# top.net
KiCad netlist of a schematic drawn in Altium Designer
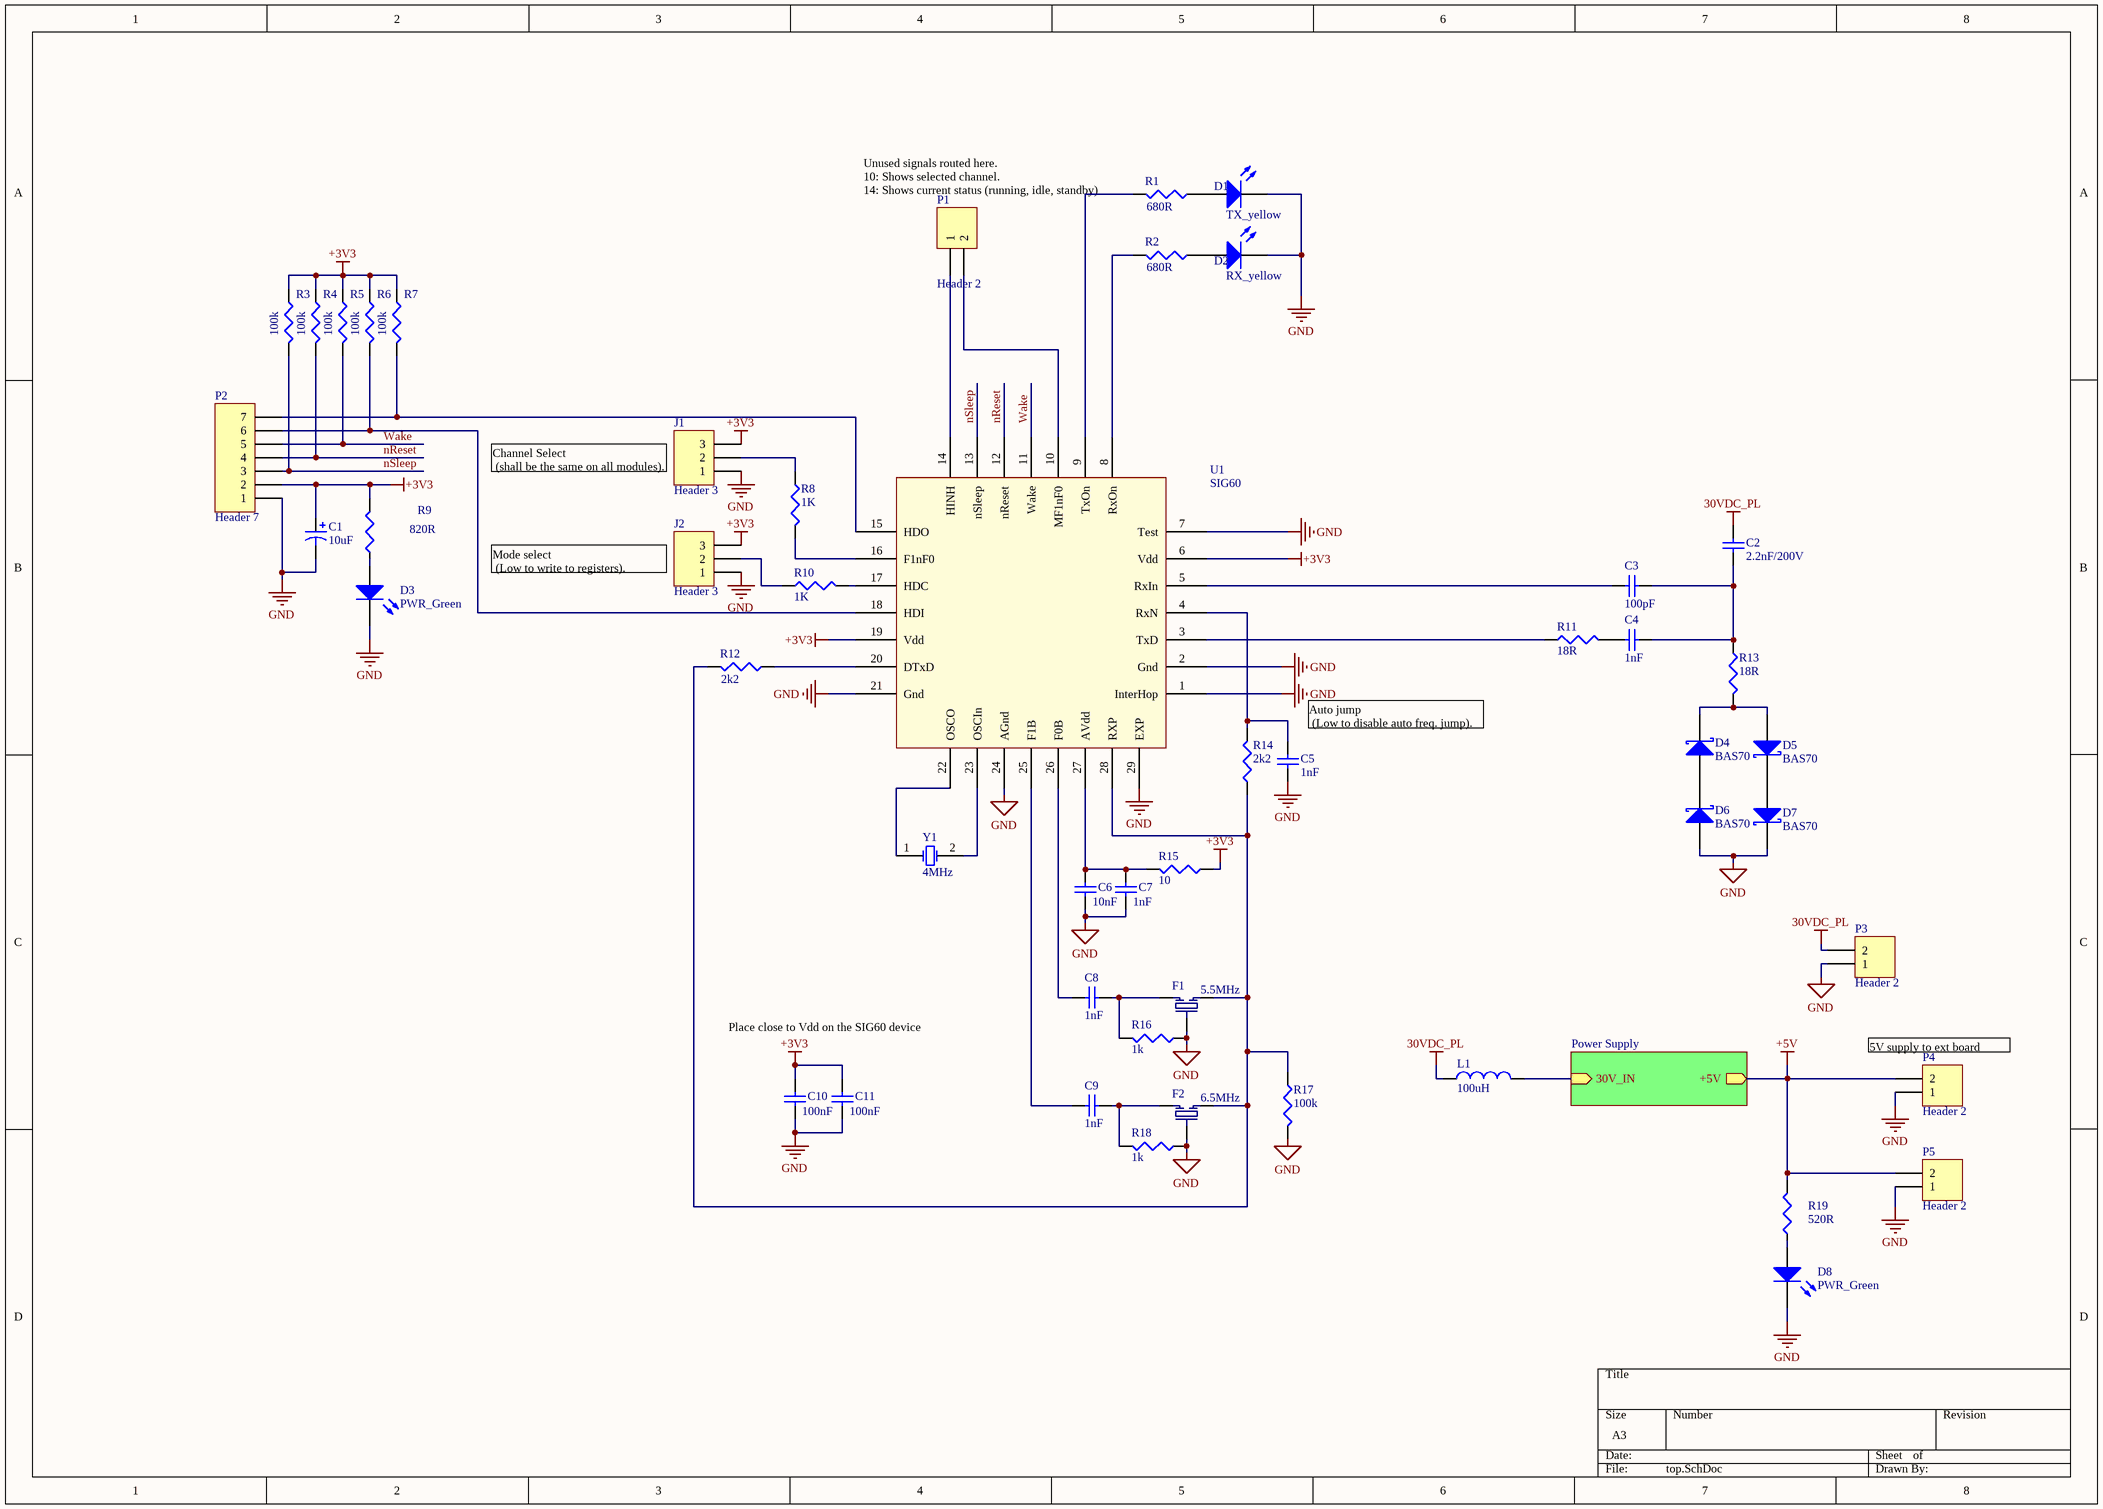
[diagram p0: top.SchDoc]

(export (version "E")
  (design (tool "Eeschema 10.0.6"))
  (components
    (comp (ref "C1")
      (value "10uF")
      (footprint "C0805")
      (description "Polarized Capacitor (Surface Mount)")
      (fields (field (name "Comment") "Cap Pol3") (field (name "PUBLISHER") "Altium Limited"))
      (libsource (lib "Miscellaneous Devices") (part "Cap Pol3"))
    )
    (comp (ref "C2")
      (value "2.2nF/200V")
      (footprint "6-0805_N")
      (description "Capacitor (Semiconductor SIM Model)")
      (fields (field (name "Comment") "Cap Semi") (field (name "PUBLISHER") "Altium Limited"))
      (libsource (lib "Miscellaneous Devices") (part "Cap Semi"))
    )
    (comp (ref "C3")
      (value "100pF")
      (footprint "6-0805_N")
      (description "Capacitor (Semiconductor SIM Model)")
      (fields (field (name "Comment") "Cap Semi") (field (name "PUBLISHER") "Altium Limited"))
      (libsource (lib "Miscellaneous Devices") (part "Cap Semi"))
    )
    (comp (ref "C4")
      (value "1nF")
      (footprint "6-0805_N")
      (description "Capacitor (Semiconductor SIM Model)")
      (fields (field (name "Comment") "Cap Semi") (field (name "PUBLISHER") "Altium Limited"))
      (libsource (lib "Miscellaneous Devices") (part "Cap Semi"))
    )
    (comp (ref "C5")
      (value "1nF")
      (footprint "6-0805_N")
      (description "Capacitor (Semiconductor SIM Model)")
      (fields (field (name "Comment") "Cap Semi") (field (name "PUBLISHER") "Altium Limited"))
      (libsource (lib "Miscellaneous Devices") (part "Cap Semi"))
    )
    (comp (ref "C6")
      (value "10nF")
      (footprint "6-0805_N")
      (description "Capacitor (Semiconductor SIM Model)")
      (fields (field (name "Comment") "Cap Semi") (field (name "PUBLISHER") "Altium Limited"))
      (libsource (lib "Miscellaneous Devices") (part "Cap Semi"))
    )
    (comp (ref "C7")
      (value "1nF")
      (footprint "6-0805_N")
      (description "Capacitor (Semiconductor SIM Model)")
      (fields (field (name "Comment") "Cap Semi") (field (name "PUBLISHER") "Altium Limited"))
      (libsource (lib "Miscellaneous Devices") (part "Cap Semi"))
    )
    (comp (ref "C8")
      (value "1nF")
      (footprint "6-0805_N")
      (description "Capacitor (Semiconductor SIM Model)")
      (fields (field (name "Comment") "Cap Semi") (field (name "PUBLISHER") "Altium Limited"))
      (libsource (lib "Miscellaneous Devices") (part "Cap Semi"))
    )
    (comp (ref "C9")
      (value "1nF")
      (footprint "6-0805_N")
      (description "Capacitor (Semiconductor SIM Model)")
      (fields (field (name "Comment") "Cap Semi") (field (name "PUBLISHER") "Altium Limited"))
      (libsource (lib "Miscellaneous Devices") (part "Cap Semi"))
    )
    (comp (ref "C10")
      (value "100nF")
      (footprint "6-0805_N")
      (description "Capacitor (Semiconductor SIM Model)")
      (fields (field (name "Comment") "Cap Semi") (field (name "PUBLISHER") "Altium Limited"))
      (libsource (lib "Miscellaneous Devices") (part "Cap Semi"))
    )
    (comp (ref "C11")
      (value "100nF")
      (footprint "6-0805_N")
      (description "Capacitor (Semiconductor SIM Model)")
      (fields (field (name "Comment") "Cap Semi") (field (name "PUBLISHER") "Altium Limited"))
      (libsource (lib "Miscellaneous Devices") (part "Cap Semi"))
    )
    (comp (ref "D1")
      (value "TX_yellow")
      (footprint "6-0805_L")
      (description "Typical RED, GREEN, YELLOW, AMBER GaAs LED")
      (fields (field (name "PUBLISHER") "Altium Limited"))
      (libsource (lib "Miscellaneous Devices") (part "LED2"))
    )
    (comp (ref "D2")
      (value "RX_yellow")
      (footprint "6-0805_L")
      (description "Typical RED, GREEN, YELLOW, AMBER GaAs LED")
      (fields (field (name "PUBLISHER") "Altium Limited"))
      (libsource (lib "Miscellaneous Devices") (part "LED2"))
    )
    (comp (ref "D3")
      (value "PWR_Green")
      (footprint "6-0805_L")
      (description "Typical RED, GREEN, YELLOW, AMBER GaAs LED")
      (fields (field (name "PUBLISHER") "Altium Limited"))
      (libsource (lib "Miscellaneous Devices") (part "LED2"))
    )
    (comp (ref "D4")
      (value "BAS70")
      (footprint "SOT-23_N")
      (description "Silicon AF Schottky Diode for High-Speed Switching")
      (fields (field (name "PUBLISHER") "Altium Limited"))
      (libsource (lib "Miscellaneous Devices") (part "Diode BAS70"))
    )
    (comp (ref "D5")
      (value "BAS70")
      (footprint "SOT-23_N")
      (description "Silicon AF Schottky Diode for High-Speed Switching")
      (fields (field (name "PUBLISHER") "Altium Limited"))
      (libsource (lib "Miscellaneous Devices") (part "Diode BAS70"))
    )
    (comp (ref "D6")
      (value "BAS70")
      (footprint "SOT-23_N")
      (description "Silicon AF Schottky Diode for High-Speed Switching")
      (fields (field (name "PUBLISHER") "Altium Limited"))
      (libsource (lib "Miscellaneous Devices") (part "Diode BAS70"))
    )
    (comp (ref "D7")
      (value "BAS70")
      (footprint "SOT-23_N")
      (description "Silicon AF Schottky Diode for High-Speed Switching")
      (fields (field (name "PUBLISHER") "Altium Limited"))
      (libsource (lib "Miscellaneous Devices") (part "Diode BAS70"))
    )
    (comp (ref "D8")
      (value "PWR_Green")
      (footprint "6-0805_L")
      (description "Typical RED, GREEN, YELLOW, AMBER GaAs LED")
      (fields (field (name "PUBLISHER") "Altium Limited"))
      (libsource (lib "Miscellaneous Devices") (part "LED2"))
    )
    (comp (ref "F1")
      (value "5.5MHz")
      (footprint "HDR1X3")
      (description "Header, 3-Pin")
      (fields (field (name "PUBLISHER") "Altium Limited"))
      (libsource (lib "new_library") (part "Ceramic Filters"))
    )
    (comp (ref "F2")
      (value "6.5MHz")
      (footprint "HDR1X3")
      (description "Header, 3-Pin")
      (fields (field (name "PUBLISHER") "Altium Limited"))
      (libsource (lib "new_library") (part "Ceramic Filters"))
    )
    (comp (ref "J1")
      (value "Header 3")
      (footprint "HDR1X3")
      (description "Header, 3-Pin")
      (fields (field (name "PUBLISHER") "Altium Limited"))
      (libsource (lib "Miscellaneous Connectors") (part "Header 3"))
    )
    (comp (ref "J2")
      (value "Header 3")
      (footprint "HDR1X3")
      (description "Header, 3-Pin")
      (fields (field (name "PUBLISHER") "Altium Limited"))
      (libsource (lib "Miscellaneous Connectors") (part "Header 3"))
    )
    (comp (ref "L1")
      (value "100uH")
      (footprint "WE_74477006")
      (description "Header, 3-Pin")
      (fields (field (name "PUBLISHER") "Altium Limited"))
      (libsource (lib "new_library") (part "Inductor"))
    )
    (comp (ref "P1")
      (value "Header 2")
      (footprint "HDR1X2")
      (description "Header, 2-Pin")
      (fields (field (name "PUBLISHER") "Altium Limited"))
      (libsource (lib "Miscellaneous Connectors") (part "Header 2"))
    )
    (comp (ref "P2")
      (value "Header 7")
      (footprint "HDR1X7")
      (description "Header, 7-Pin")
      (fields (field (name "PUBLISHER") "Altium Limited"))
      (libsource (lib "Miscellaneous Connectors") (part "Header 7"))
    )
    (comp (ref "P3")
      (value "Header 2")
      (footprint "HDR1X2")
      (description "Header, 2-Pin")
      (fields (field (name "PUBLISHER") "Altium Limited"))
      (libsource (lib "Miscellaneous Connectors") (part "Header 2"))
    )
    (comp (ref "P4")
      (value "Header 2")
      (footprint "HDR1X2")
      (description "Header, 2-Pin")
      (fields (field (name "PUBLISHER") "Altium Limited"))
      (libsource (lib "Miscellaneous Connectors") (part "Header 2"))
    )
    (comp (ref "P5")
      (value "Header 2")
      (footprint "HDR1X2")
      (description "Header, 2-Pin")
      (fields (field (name "PUBLISHER") "Altium Limited"))
      (libsource (lib "Miscellaneous Connectors") (part "Header 2"))
    )
    (comp (ref "R1")
      (value "680R")
      (footprint "6-0805_L")
      (description "Resistor")
      (fields (field (name "Comment") "Res3") (field (name "PUBLISHER") "Altium Limited"))
      (libsource (lib "Miscellaneous Devices") (part "Res3"))
    )
    (comp (ref "R2")
      (value "680R")
      (footprint "6-0805_L")
      (description "Resistor")
      (fields (field (name "Comment") "Res3") (field (name "PUBLISHER") "Altium Limited"))
      (libsource (lib "Miscellaneous Devices") (part "Res3"))
    )
    (comp (ref "R3")
      (value "100k")
      (footprint "6-0805_L")
      (description "Resistor")
      (fields (field (name "Comment") "Res3") (field (name "PUBLISHER") "Altium Limited"))
      (libsource (lib "Miscellaneous Devices") (part "Res3"))
    )
    (comp (ref "R4")
      (value "100k")
      (footprint "6-0805_L")
      (description "Resistor")
      (fields (field (name "Comment") "Res3") (field (name "PUBLISHER") "Altium Limited"))
      (libsource (lib "Miscellaneous Devices") (part "Res3"))
    )
    (comp (ref "R5")
      (value "100k")
      (footprint "6-0805_L")
      (description "Resistor")
      (fields (field (name "Comment") "Res3") (field (name "PUBLISHER") "Altium Limited"))
      (libsource (lib "Miscellaneous Devices") (part "Res3"))
    )
    (comp (ref "R6")
      (value "100k")
      (footprint "6-0805_L")
      (description "Resistor")
      (fields (field (name "Comment") "Res3") (field (name "PUBLISHER") "Altium Limited"))
      (libsource (lib "Miscellaneous Devices") (part "Res3"))
    )
    (comp (ref "R7")
      (value "100k")
      (footprint "6-0805_L")
      (description "Resistor")
      (fields (field (name "Comment") "Res3") (field (name "PUBLISHER") "Altium Limited"))
      (libsource (lib "Miscellaneous Devices") (part "Res3"))
    )
    (comp (ref "R8")
      (value "1K")
      (footprint "6-0805_L")
      (description "Resistor")
      (fields (field (name "Comment") "Res3") (field (name "PUBLISHER") "Altium Limited"))
      (libsource (lib "Miscellaneous Devices") (part "Res3"))
    )
    (comp (ref "R9")
      (value "820R")
      (footprint "6-0805_L")
      (description "Resistor")
      (fields (field (name "Comment") "Res3") (field (name "PUBLISHER") "Altium Limited"))
      (libsource (lib "Miscellaneous Devices") (part "Res3"))
    )
    (comp (ref "R10")
      (value "1K")
      (footprint "6-0805_L")
      (description "Resistor")
      (fields (field (name "Comment") "Res3") (field (name "PUBLISHER") "Altium Limited"))
      (libsource (lib "Miscellaneous Devices") (part "Res3"))
    )
    (comp (ref "R11")
      (value "18R")
      (footprint "6-0805_L")
      (description "Resistor")
      (fields (field (name "Comment") "Res3") (field (name "PUBLISHER") "Altium Limited"))
      (libsource (lib "Miscellaneous Devices") (part "Res3"))
    )
    (comp (ref "R12")
      (value "2k2")
      (footprint "6-0805_L")
      (description "Resistor")
      (fields (field (name "Comment") "Res3") (field (name "PUBLISHER") "Altium Limited"))
      (libsource (lib "Miscellaneous Devices") (part "Res3"))
    )
    (comp (ref "R13")
      (value "18R")
      (footprint "6-0805_L")
      (description "Resistor")
      (fields (field (name "Comment") "Res3") (field (name "PUBLISHER") "Altium Limited"))
      (libsource (lib "Miscellaneous Devices") (part "Res3"))
    )
    (comp (ref "R14")
      (value "2k2")
      (footprint "6-0805_L")
      (description "Resistor")
      (fields (field (name "Comment") "Res3") (field (name "PUBLISHER") "Altium Limited"))
      (libsource (lib "Miscellaneous Devices") (part "Res3"))
    )
    (comp (ref "R15")
      (value "10")
      (footprint "6-0805_L")
      (description "Resistor")
      (fields (field (name "Comment") "Res3") (field (name "PUBLISHER") "Altium Limited"))
      (libsource (lib "Miscellaneous Devices") (part "Res3"))
    )
    (comp (ref "R16")
      (value "1k")
      (footprint "6-0805_L")
      (description "Resistor")
      (fields (field (name "Comment") "Res3") (field (name "PUBLISHER") "Altium Limited"))
      (libsource (lib "Miscellaneous Devices") (part "Res3"))
    )
    (comp (ref "R17")
      (value "100k")
      (footprint "6-0805_L")
      (description "Resistor")
      (fields (field (name "Comment") "Res3") (field (name "PUBLISHER") "Altium Limited"))
      (libsource (lib "Miscellaneous Devices") (part "Res3"))
    )
    (comp (ref "R18")
      (value "1k")
      (footprint "6-0805_L")
      (description "Resistor")
      (fields (field (name "Comment") "Res3") (field (name "PUBLISHER") "Altium Limited"))
      (libsource (lib "Miscellaneous Devices") (part "Res3"))
    )
    (comp (ref "R19")
      (value "520R")
      (footprint "6-0805_L")
      (description "Resistor")
      (fields (field (name "Comment") "Res3") (field (name "PUBLISHER") "Altium Limited"))
      (libsource (lib "Miscellaneous Devices") (part "Res3"))
    )
    (comp (ref "U1")
      (value "SIG60")
      (footprint "QFN65P600X600X90-28N")
      (description "SIG60 device. UART to PLC device.")
      (libsource (lib "new_library") (part "SIG60"))
    )
    (comp (ref "Y1")
      (value "4MHz")
      (footprint "R38")
      (description "Crystal Oscillator")
      (fields (field (name "PUBLISHER") "Altium Limited"))
      (libsource (lib "Miscellaneous Devices") (part "XTAL"))
    )
  )
  (nets
    (net (code "1") (name "+3V3") (class "Default")
      (node (ref "C1") (pin "1") (pinfunction "1_1") (pintype "passive"))
      (node (ref "C10") (pin "2") (pinfunction "2_2") (pintype "passive"))
      (node (ref "C11") (pin "2") (pinfunction "2_2") (pintype "passive"))
      (node (ref "J1") (pin "3") (pinfunction "3_3") (pintype "passive"))
      (node (ref "J2") (pin "3") (pinfunction "3_3") (pintype "passive"))
      (node (ref "P2") (pin "2") (pinfunction "2_2") (pintype "passive"))
      (node (ref "R15") (pin "1") (pinfunction "1_1") (pintype "passive"))
      (node (ref "R3") (pin "1") (pinfunction "1_1") (pintype "passive"))
      (node (ref "R4") (pin "1") (pinfunction "1_1") (pintype "passive"))
      (node (ref "R5") (pin "1") (pinfunction "1_1") (pintype "passive"))
      (node (ref "R6") (pin "1") (pinfunction "1_1") (pintype "passive"))
      (node (ref "R7") (pin "1") (pinfunction "1_1") (pintype "passive"))
      (node (ref "R9") (pin "2") (pinfunction "2_2") (pintype "passive"))
      (node (ref "U1") (pin "19") (pinfunction "Vdd_19") (pintype "power_in"))
      (node (ref "U1") (pin "6") (pinfunction "Vdd_6") (pintype "power_in"))
    )
    (net (code "2") (name "+5V") (class "Default")
      (node (ref "P4") (pin "2") (pinfunction "2_2") (pintype "passive"))
      (node (ref "P5") (pin "2") (pinfunction "2_2") (pintype "passive"))
      (node (ref "R19") (pin "2") (pinfunction "2_2") (pintype "passive"))
    )
    (net (code "3") (name "/30V_IN") (class "Default")
      (node (ref "L1") (pin "2") (pinfunction "2_2") (pintype "passive"))
    )
    (net (code "4") (name "/Wake") (class "Default")
      (node (ref "P2") (pin "5") (pinfunction "5_5") (pintype "passive"))
      (node (ref "R5") (pin "2") (pinfunction "2_2") (pintype "passive"))
      (node (ref "U1") (pin "11") (pinfunction "Wake_11") (pintype "passive"))
    )
    (net (code "5") (name "/nReset") (class "Default")
      (node (ref "P2") (pin "4") (pinfunction "4_4") (pintype "passive"))
      (node (ref "R4") (pin "2") (pinfunction "2_2") (pintype "passive"))
      (node (ref "U1") (pin "12") (pinfunction "nReset_12") (pintype "passive"))
    )
    (net (code "6") (name "/nSleep") (class "Default")
      (node (ref "P2") (pin "3") (pinfunction "3_3") (pintype "passive"))
      (node (ref "R3") (pin "2") (pinfunction "2_2") (pintype "passive"))
      (node (ref "U1") (pin "13") (pinfunction "nSleep_13") (pintype "passive"))
    )
    (net (code "7") (name "30VDC_PL") (class "Default")
      (node (ref "C2") (pin "2") (pinfunction "2_2") (pintype "passive"))
      (node (ref "L1") (pin "1") (pinfunction "1_1") (pintype "passive"))
      (node (ref "P3") (pin "2") (pinfunction "2_2") (pintype "passive"))
    )
    (net (code "8") (name "GND") (class "Default")
      (node (ref "C1") (pin "2") (pinfunction "2_2") (pintype "passive"))
      (node (ref "C10") (pin "1") (pinfunction "1_1") (pintype "passive"))
      (node (ref "C11") (pin "1") (pinfunction "1_1") (pintype "passive"))
      (node (ref "C5") (pin "1") (pinfunction "1_1") (pintype "passive"))
      (node (ref "C6") (pin "1") (pinfunction "1_1") (pintype "passive"))
      (node (ref "C7") (pin "1") (pinfunction "1_1") (pintype "passive"))
      (node (ref "D1") (pin "2") (pinfunction "K_2") (pintype "passive"))
      (node (ref "D2") (pin "2") (pinfunction "K_2") (pintype "passive"))
      (node (ref "D3") (pin "2") (pinfunction "K_2") (pintype "passive"))
      (node (ref "D6") (pin "1") (pinfunction "A_1") (pintype "passive"))
      (node (ref "D7") (pin "3") (pinfunction "K_3") (pintype "passive"))
      (node (ref "D8") (pin "2") (pinfunction "K_2") (pintype "passive"))
      (node (ref "F1") (pin "2") (pinfunction "2_2") (pintype "passive"))
      (node (ref "F2") (pin "2") (pinfunction "2_2") (pintype "passive"))
      (node (ref "J1") (pin "1") (pinfunction "1_1") (pintype "passive"))
      (node (ref "J2") (pin "1") (pinfunction "1_1") (pintype "passive"))
      (node (ref "P2") (pin "1") (pinfunction "1_1") (pintype "passive"))
      (node (ref "P3") (pin "1") (pinfunction "1_1") (pintype "passive"))
      (node (ref "P4") (pin "1") (pinfunction "1_1") (pintype "passive"))
      (node (ref "P5") (pin "1") (pinfunction "1_1") (pintype "passive"))
      (node (ref "R16") (pin "1") (pinfunction "1_1") (pintype "passive"))
      (node (ref "R17") (pin "2") (pinfunction "2_2") (pintype "passive"))
      (node (ref "R18") (pin "1") (pinfunction "1_1") (pintype "passive"))
      (node (ref "U1") (pin "1") (pinfunction "InterHop_1") (pintype "passive"))
      (node (ref "U1") (pin "2") (pinfunction "Gnd_2") (pintype "power_in"))
      (node (ref "U1") (pin "21") (pinfunction "Gnd_21") (pintype "power_in"))
      (node (ref "U1") (pin "24") (pinfunction "AGnd_24") (pintype "power_in"))
      (node (ref "U1") (pin "29") (pinfunction "EXP_29") (pintype "passive"))
      (node (ref "U1") (pin "7") (pinfunction "Test_7") (pintype "passive"))
    )
    (net (code "9") (name "Net-(C2-Pad1)") (class "Default")
      (node (ref "C2") (pin "1") (pinfunction "1_1") (pintype "passive"))
      (node (ref "C3") (pin "1") (pinfunction "1_1") (pintype "passive"))
      (node (ref "C4") (pin "1") (pinfunction "1_1") (pintype "passive"))
      (node (ref "R13") (pin "1") (pinfunction "1_1") (pintype "passive"))
    )
    (net (code "10") (name "Net-(C4-Pad2)") (class "Default")
      (node (ref "C4") (pin "2") (pinfunction "2_2") (pintype "passive"))
      (node (ref "R11") (pin "2") (pinfunction "2_2") (pintype "passive"))
    )
    (net (code "11") (name "Net-(C8-Pad1)") (class "Default")
      (node (ref "C8") (pin "1") (pinfunction "1_1") (pintype "passive"))
      (node (ref "F1") (pin "1") (pinfunction "1_1") (pintype "passive"))
      (node (ref "R16") (pin "2") (pinfunction "2_2") (pintype "passive"))
    )
    (net (code "12") (name "Net-(C9-Pad1)") (class "Default")
      (node (ref "C9") (pin "1") (pinfunction "1_1") (pintype "passive"))
      (node (ref "F2") (pin "1") (pinfunction "1_1") (pintype "passive"))
      (node (ref "R18") (pin "2") (pinfunction "2_2") (pintype "passive"))
    )
    (net (code "13") (name "Net-(D1-A)") (class "Default")
      (node (ref "D1") (pin "1") (pinfunction "A_1") (pintype "passive"))
      (node (ref "R1") (pin "1") (pinfunction "1_1") (pintype "passive"))
    )
    (net (code "14") (name "Net-(D2-A)") (class "Default")
      (node (ref "D2") (pin "1") (pinfunction "A_1") (pintype "passive"))
      (node (ref "R2") (pin "1") (pinfunction "1_1") (pintype "passive"))
    )
    (net (code "15") (name "Net-(D3-A)") (class "Default")
      (node (ref "D3") (pin "1") (pinfunction "A_1") (pintype "passive"))
      (node (ref "R9") (pin "1") (pinfunction "1_1") (pintype "passive"))
    )
    (net (code "16") (name "Net-(D4-A)") (class "Default")
      (node (ref "D4") (pin "1") (pinfunction "A_1") (pintype "passive"))
      (node (ref "D6") (pin "3") (pinfunction "K_3") (pintype "passive"))
    )
    (net (code "17") (name "Net-(D4-K)") (class "Default")
      (node (ref "D4") (pin "3") (pinfunction "K_3") (pintype "passive"))
      (node (ref "D5") (pin "1") (pinfunction "A_1") (pintype "passive"))
      (node (ref "R13") (pin "2") (pinfunction "2_2") (pintype "passive"))
    )
    (net (code "18") (name "Net-(D5-K)") (class "Default")
      (node (ref "D5") (pin "3") (pinfunction "K_3") (pintype "passive"))
      (node (ref "D7") (pin "1") (pinfunction "A_1") (pintype "passive"))
    )
    (net (code "19") (name "Net-(D8-A)") (class "Default")
      (node (ref "D8") (pin "1") (pinfunction "A_1") (pintype "passive"))
      (node (ref "R19") (pin "1") (pinfunction "1_1") (pintype "passive"))
    )
    (net (code "20") (name "Net-(J1-Pad2)") (class "Default")
      (node (ref "J1") (pin "2") (pinfunction "2_2") (pintype "passive"))
      (node (ref "R8") (pin "1") (pinfunction "1_1") (pintype "passive"))
    )
    (net (code "21") (name "Net-(J2-Pad2)") (class "Default")
      (node (ref "J2") (pin "2") (pinfunction "2_2") (pintype "passive"))
      (node (ref "R10") (pin "1") (pinfunction "1_1") (pintype "passive"))
    )
    (net (code "22") (name "Net-(U1-AVdd)") (class "Default")
      (node (ref "C6") (pin "2") (pinfunction "2_2") (pintype "passive"))
      (node (ref "C7") (pin "2") (pinfunction "2_2") (pintype "passive"))
      (node (ref "R15") (pin "2") (pinfunction "2_2") (pintype "passive"))
      (node (ref "U1") (pin "27") (pinfunction "AVdd_27") (pintype "power_in"))
    )
    (net (code "23") (name "Net-(U1-DTxD)") (class "Default")
      (node (ref "R12") (pin "1") (pinfunction "1_1") (pintype "passive"))
      (node (ref "U1") (pin "20") (pinfunction "DTxD_20") (pintype "passive"))
    )
    (net (code "24") (name "Net-(U1-F0B)") (class "Default")
      (node (ref "C8") (pin "2") (pinfunction "2_2") (pintype "passive"))
      (node (ref "U1") (pin "26") (pinfunction "F0B_26") (pintype "passive"))
    )
    (net (code "25") (name "Net-(U1-F1B)") (class "Default")
      (node (ref "C9") (pin "2") (pinfunction "2_2") (pintype "passive"))
      (node (ref "U1") (pin "25") (pinfunction "F1B_25") (pintype "passive"))
    )
    (net (code "26") (name "Net-(U1-F1nF0)") (class "Default")
      (node (ref "R8") (pin "2") (pinfunction "2_2") (pintype "passive"))
      (node (ref "U1") (pin "16") (pinfunction "F1nF0_16") (pintype "passive"))
    )
    (net (code "27") (name "Net-(U1-HDC)") (class "Default")
      (node (ref "R10") (pin "2") (pinfunction "2_2") (pintype "passive"))
      (node (ref "U1") (pin "17") (pinfunction "HDC_17") (pintype "passive"))
    )
    (net (code "28") (name "Net-(U1-HDI)") (class "Default")
      (node (ref "P2") (pin "6") (pinfunction "6_6") (pintype "passive"))
      (node (ref "R6") (pin "2") (pinfunction "2_2") (pintype "passive"))
      (node (ref "U1") (pin "18") (pinfunction "HDI_18") (pintype "passive"))
    )
    (net (code "29") (name "Net-(U1-HDO)") (class "Default")
      (node (ref "P2") (pin "7") (pinfunction "7_7") (pintype "passive"))
      (node (ref "R7") (pin "2") (pinfunction "2_2") (pintype "passive"))
      (node (ref "U1") (pin "15") (pinfunction "HDO_15") (pintype "passive"))
    )
    (net (code "30") (name "Net-(U1-HINH)") (class "Default")
      (node (ref "P1") (pin "1") (pinfunction "1_1") (pintype "passive"))
      (node (ref "U1") (pin "14") (pinfunction "HINH_14") (pintype "passive"))
    )
    (net (code "31") (name "Net-(U1-MF1nF0)") (class "Default")
      (node (ref "P1") (pin "2") (pinfunction "2_2") (pintype "passive"))
      (node (ref "U1") (pin "10") (pinfunction "MF1nF0_10") (pintype "passive"))
    )
    (net (code "32") (name "Net-(U1-OSCIn)") (class "Default")
      (node (ref "U1") (pin "23") (pinfunction "OSCIn_23") (pintype "passive"))
      (node (ref "Y1") (pin "2") (pinfunction "OSC2_2") (pintype "passive"))
    )
    (net (code "33") (name "Net-(U1-OSCO)") (class "Default")
      (node (ref "U1") (pin "22") (pinfunction "OSCO_22") (pintype "passive"))
      (node (ref "Y1") (pin "1") (pinfunction "OSC1_1") (pintype "passive"))
    )
    (net (code "34") (name "Net-(U1-RXP)") (class "Default")
      (node (ref "F1") (pin "3") (pinfunction "3_3") (pintype "passive"))
      (node (ref "F2") (pin "3") (pinfunction "3_3") (pintype "passive"))
      (node (ref "R12") (pin "2") (pinfunction "2_2") (pintype "passive"))
      (node (ref "R14") (pin "1") (pinfunction "1_1") (pintype "passive"))
      (node (ref "R17") (pin "1") (pinfunction "1_1") (pintype "passive"))
      (node (ref "U1") (pin "28") (pinfunction "RXP_28") (pintype "passive"))
    )
    (net (code "35") (name "Net-(U1-RxIn)") (class "Default")
      (node (ref "C3") (pin "2") (pinfunction "2_2") (pintype "passive"))
      (node (ref "U1") (pin "5") (pinfunction "RxIn_5") (pintype "passive"))
    )
    (net (code "36") (name "Net-(U1-RxN)") (class "Default")
      (node (ref "C5") (pin "2") (pinfunction "2_2") (pintype "passive"))
      (node (ref "R14") (pin "2") (pinfunction "2_2") (pintype "passive"))
      (node (ref "U1") (pin "4") (pinfunction "RxN_4") (pintype "passive"))
    )
    (net (code "37") (name "Net-(U1-RxOn)") (class "Default")
      (node (ref "R2") (pin "2") (pinfunction "2_2") (pintype "passive"))
      (node (ref "U1") (pin "8") (pinfunction "RxOn_8") (pintype "passive"))
    )
    (net (code "38") (name "Net-(U1-TxD)") (class "Default")
      (node (ref "R11") (pin "1") (pinfunction "1_1") (pintype "passive"))
      (node (ref "U1") (pin "3") (pinfunction "TxD_3") (pintype "passive"))
    )
    (net (code "39") (name "Net-(U1-TxOn)") (class "Default")
      (node (ref "R1") (pin "2") (pinfunction "2_2") (pintype "passive"))
      (node (ref "U1") (pin "9") (pinfunction "TxOn_9") (pintype "passive"))
    )
  )
)
